# draft4_4lyr.net
KiCad netlist of a schematic drawn in EAGLE
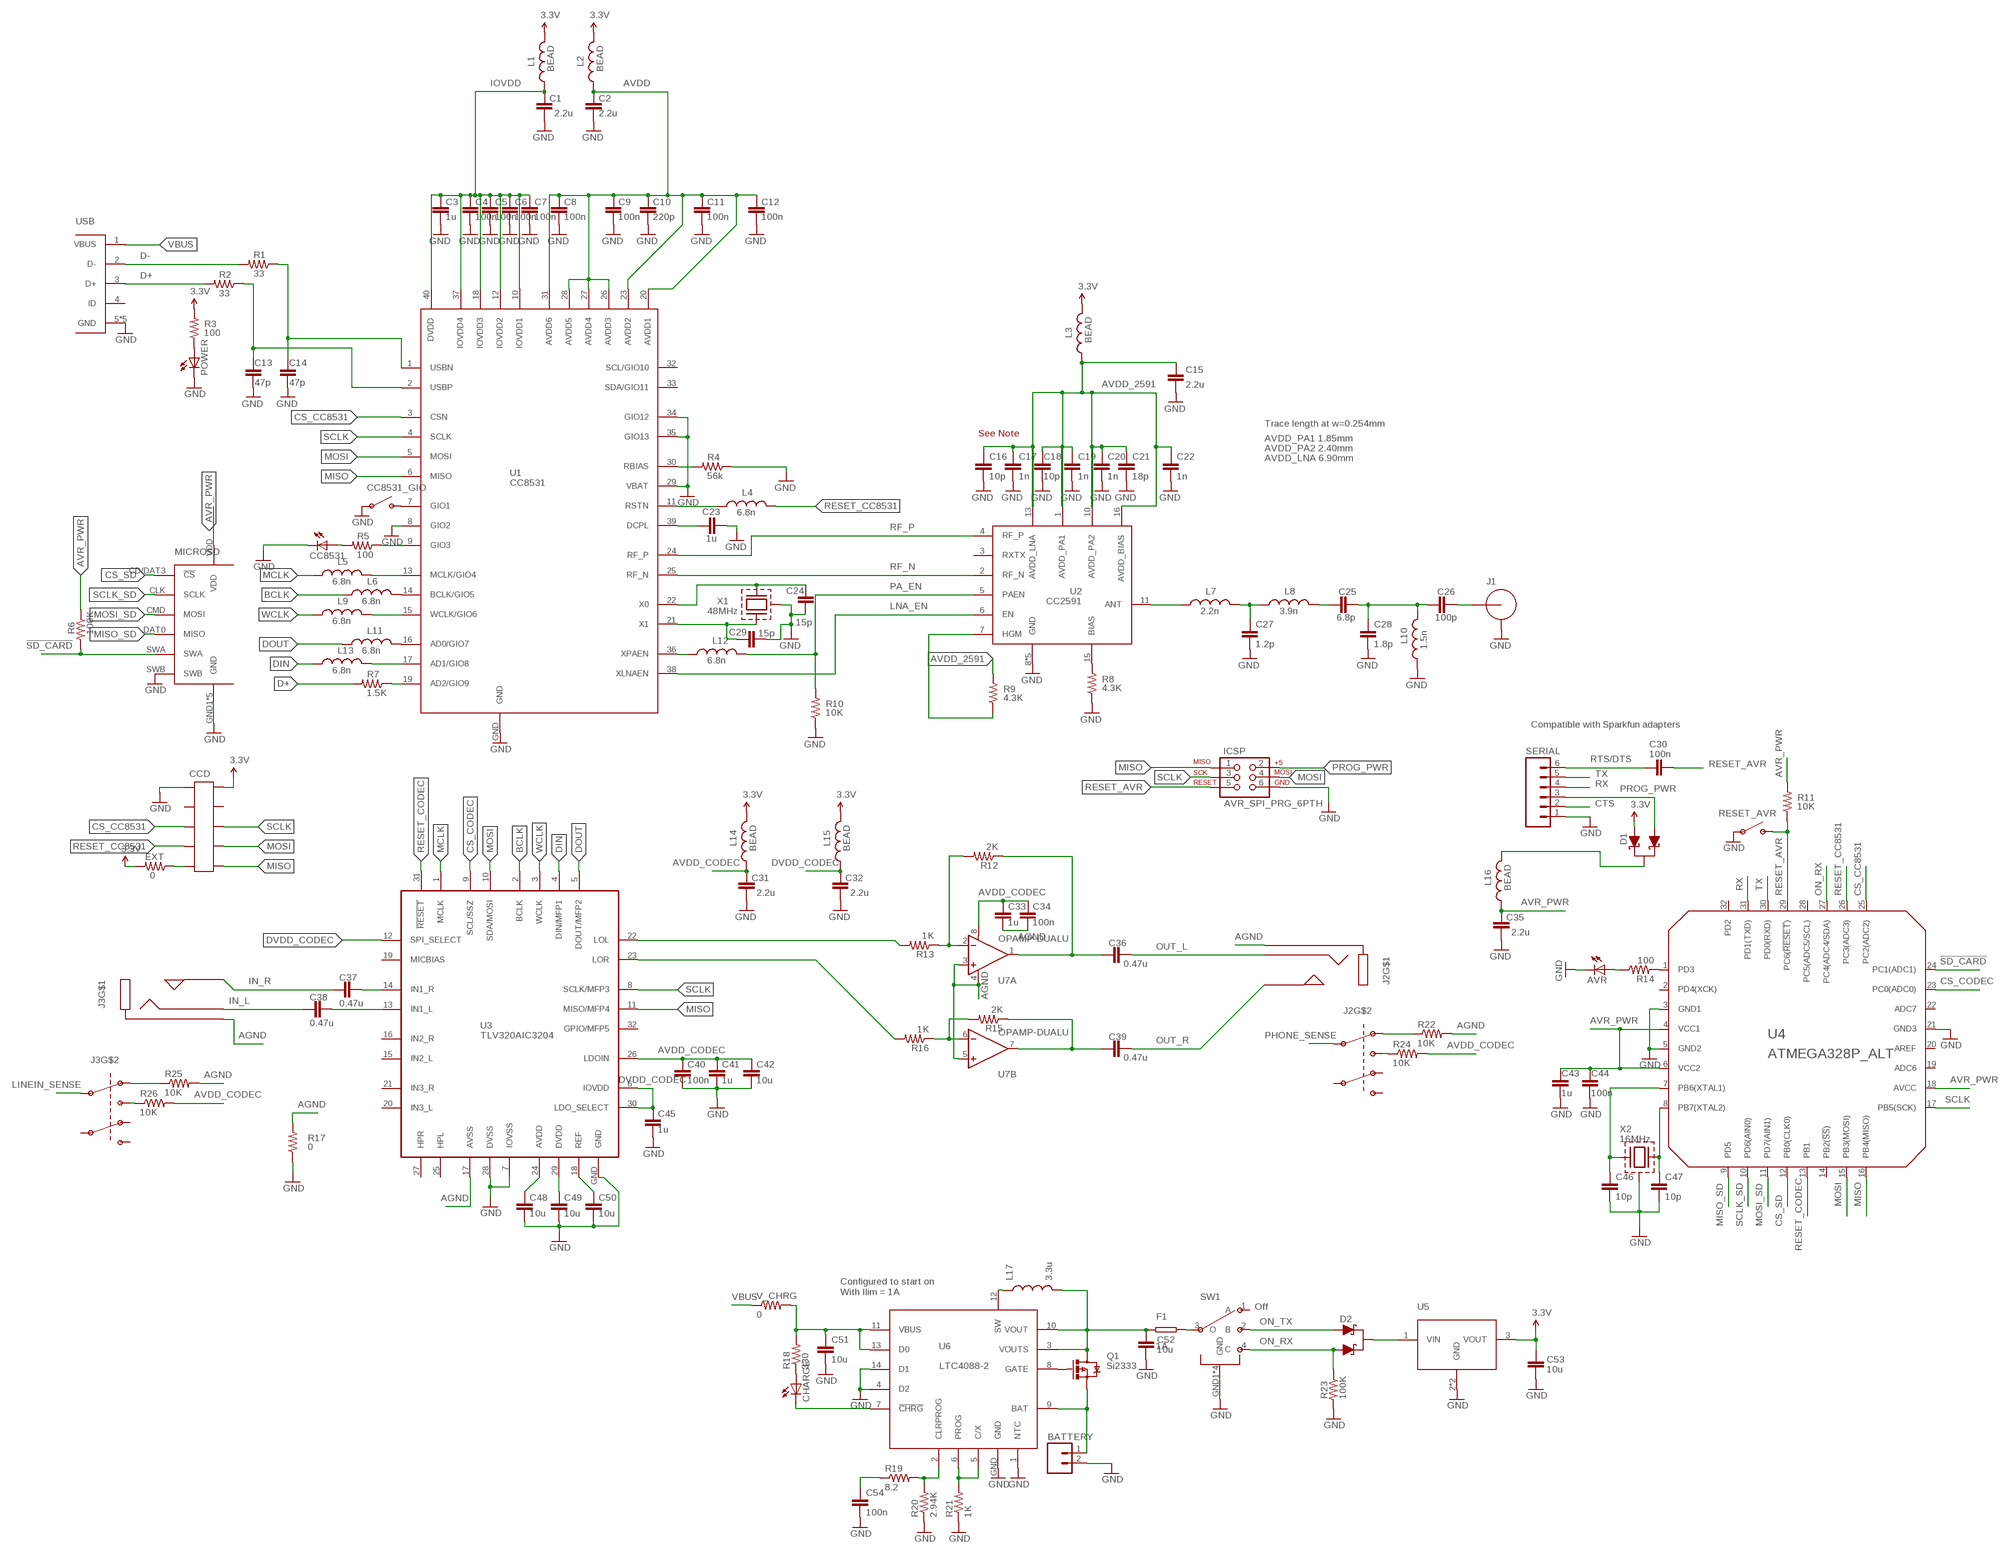
[diagram p0: schematic, sheet 1]

(export (version "E")
  (design (tool "Eeschema 10.0.6"))
  (components
    (comp (ref "AVR")
      (value "LED1206")
      (footprint "eagle-import:LED-1206")
      (libsource (lib "eagle-import") (part "LED1206"))
    )
    (comp (ref "BATTERY")
      (value "M02-JST-2MM-SMT")
      (footprint "eagle-import:JST-2-SMD")
      (libsource (lib "eagle-import") (part "M02-JST-2MM-SMT"))
    )
    (comp (ref "C1")
      (value "2.2u")
      (footprint "eagle-import:C0603")
      (libsource (lib "eagle-import") (part "rcl_C-EUC0603"))
    )
    (comp (ref "C2")
      (value "2.2u")
      (footprint "eagle-import:C0603")
      (libsource (lib "eagle-import") (part "rcl_C-EUC0603"))
    )
    (comp (ref "C3")
      (value "1u")
      (footprint "eagle-import:C0603")
      (libsource (lib "eagle-import") (part "rcl_C-EUC0603"))
    )
    (comp (ref "C4")
      (value "100n")
      (footprint "eagle-import:C0603")
      (libsource (lib "eagle-import") (part "rcl_C-EUC0603"))
    )
    (comp (ref "C5")
      (value "100n")
      (footprint "eagle-import:C0603")
      (libsource (lib "eagle-import") (part "rcl_C-EUC0603"))
    )
    (comp (ref "C6")
      (value "100n")
      (footprint "eagle-import:C0603")
      (libsource (lib "eagle-import") (part "rcl_C-EUC0603"))
    )
    (comp (ref "C7")
      (value "100n")
      (footprint "eagle-import:C0603")
      (libsource (lib "eagle-import") (part "rcl_C-EUC0603"))
    )
    (comp (ref "C8")
      (value "100n")
      (footprint "eagle-import:C0603")
      (libsource (lib "eagle-import") (part "rcl_C-EUC0603"))
    )
    (comp (ref "C9")
      (value "100n")
      (footprint "eagle-import:C0603")
      (libsource (lib "eagle-import") (part "rcl_C-EUC0603"))
    )
    (comp (ref "C10")
      (value "220p")
      (footprint "eagle-import:C0603")
      (libsource (lib "eagle-import") (part "rcl_C-EUC0603"))
    )
    (comp (ref "C11")
      (value "100n")
      (footprint "eagle-import:C0603")
      (libsource (lib "eagle-import") (part "rcl_C-EUC0603"))
    )
    (comp (ref "C12")
      (value "100n")
      (footprint "eagle-import:C0603")
      (libsource (lib "eagle-import") (part "rcl_C-EUC0603"))
    )
    (comp (ref "C13")
      (value "47p")
      (footprint "eagle-import:C0603")
      (libsource (lib "eagle-import") (part "rcl_C-EUC0603"))
    )
    (comp (ref "C14")
      (value "47p")
      (footprint "eagle-import:C0603")
      (libsource (lib "eagle-import") (part "rcl_C-EUC0603"))
    )
    (comp (ref "C15")
      (value "2.2u")
      (footprint "eagle-import:C0603")
      (libsource (lib "eagle-import") (part "rcl_C-EUC0603"))
    )
    (comp (ref "C16")
      (value "10p")
      (footprint "eagle-import:C0603")
      (libsource (lib "eagle-import") (part "rcl_C-EUC0603"))
    )
    (comp (ref "C17")
      (value "1n")
      (footprint "eagle-import:C0603")
      (libsource (lib "eagle-import") (part "rcl_C-EUC0603"))
    )
    (comp (ref "C18")
      (value "10p")
      (footprint "eagle-import:C0603")
      (libsource (lib "eagle-import") (part "rcl_C-EUC0603"))
    )
    (comp (ref "C19")
      (value "1n")
      (footprint "eagle-import:C0603")
      (libsource (lib "eagle-import") (part "rcl_C-EUC0603"))
    )
    (comp (ref "C20")
      (value "1n")
      (footprint "eagle-import:C0603")
      (libsource (lib "eagle-import") (part "rcl_C-EUC0603"))
    )
    (comp (ref "C21")
      (value "18p")
      (footprint "eagle-import:C0603")
      (libsource (lib "eagle-import") (part "rcl_C-EUC0603"))
    )
    (comp (ref "C22")
      (value "1n")
      (footprint "eagle-import:C0603")
      (libsource (lib "eagle-import") (part "rcl_C-EUC0603"))
    )
    (comp (ref "C23")
      (value "1u")
      (footprint "eagle-import:C0603")
      (libsource (lib "eagle-import") (part "rcl_C-EUC0603"))
    )
    (comp (ref "C24")
      (value "15p")
      (footprint "eagle-import:C0603")
      (libsource (lib "eagle-import") (part "rcl_C-EUC0603"))
    )
    (comp (ref "C25")
      (value "6.8p")
      (footprint "eagle-import:C0603")
      (libsource (lib "eagle-import") (part "rcl_C-EUC0603"))
    )
    (comp (ref "C26")
      (value "100p")
      (footprint "eagle-import:C0603")
      (libsource (lib "eagle-import") (part "rcl_C-EUC0603"))
    )
    (comp (ref "C27")
      (value "1.2p")
      (footprint "eagle-import:C0603")
      (libsource (lib "eagle-import") (part "rcl_C-EUC0603"))
    )
    (comp (ref "C28")
      (value "1.8p")
      (footprint "eagle-import:C0603")
      (libsource (lib "eagle-import") (part "rcl_C-EUC0603"))
    )
    (comp (ref "C29")
      (value "15p")
      (footprint "eagle-import:C0603")
      (libsource (lib "eagle-import") (part "rcl_C-EUC0603"))
    )
    (comp (ref "C30")
      (value "100n")
      (footprint "eagle-import:C0603")
      (libsource (lib "eagle-import") (part "rcl_C-EUC0603"))
    )
    (comp (ref "C31")
      (value "2.2u")
      (footprint "eagle-import:C0603")
      (libsource (lib "eagle-import") (part "rcl_C-EUC0603"))
    )
    (comp (ref "C32")
      (value "2.2u")
      (footprint "eagle-import:C0603")
      (libsource (lib "eagle-import") (part "rcl_C-EUC0603"))
    )
    (comp (ref "C33")
      (value "1u")
      (footprint "eagle-import:C0603")
      (libsource (lib "eagle-import") (part "rcl_C-EUC0603"))
    )
    (comp (ref "C34")
      (value "100n")
      (footprint "eagle-import:C0603")
      (libsource (lib "eagle-import") (part "rcl_C-EUC0603"))
    )
    (comp (ref "C35")
      (value "2.2u")
      (footprint "eagle-import:C0603")
      (libsource (lib "eagle-import") (part "rcl_C-EUC0603"))
    )
    (comp (ref "C36")
      (value "0.47u")
      (footprint "eagle-import:C0603")
      (libsource (lib "eagle-import") (part "rcl_C-EUC0603"))
    )
    (comp (ref "C37")
      (value "0.47u")
      (footprint "eagle-import:C0603")
      (libsource (lib "eagle-import") (part "rcl_C-EUC0603"))
    )
    (comp (ref "C38")
      (value "0.47u")
      (footprint "eagle-import:C0603")
      (libsource (lib "eagle-import") (part "rcl_C-EUC0603"))
    )
    (comp (ref "C39")
      (value "0.47u")
      (footprint "eagle-import:C0603")
      (libsource (lib "eagle-import") (part "rcl_C-EUC0603"))
    )
    (comp (ref "C40")
      (value "100n")
      (footprint "eagle-import:C0603")
      (libsource (lib "eagle-import") (part "rcl_C-EUC0603"))
    )
    (comp (ref "C41")
      (value "1u")
      (footprint "eagle-import:C0603")
      (libsource (lib "eagle-import") (part "rcl_C-EUC0603"))
    )
    (comp (ref "C42")
      (value "10u")
      (footprint "eagle-import:C0603")
      (libsource (lib "eagle-import") (part "rcl_C-EUC0603"))
    )
    (comp (ref "C43")
      (value "1u")
      (footprint "eagle-import:C0603")
      (libsource (lib "eagle-import") (part "rcl_C-EUC0603"))
    )
    (comp (ref "C44")
      (value "100n")
      (footprint "eagle-import:C0603")
      (libsource (lib "eagle-import") (part "rcl_C-EUC0603"))
    )
    (comp (ref "C45")
      (value "1u")
      (footprint "eagle-import:C0603")
      (libsource (lib "eagle-import") (part "rcl_C-EUC0603"))
    )
    (comp (ref "C46")
      (value "10p")
      (footprint "eagle-import:C0603")
      (libsource (lib "eagle-import") (part "C-EUC0603"))
    )
    (comp (ref "C47")
      (value "10p")
      (footprint "eagle-import:C0603")
      (libsource (lib "eagle-import") (part "C-EUC0603"))
    )
    (comp (ref "C48")
      (value "10u")
      (footprint "eagle-import:C0603")
      (libsource (lib "eagle-import") (part "rcl_C-EUC0603"))
    )
    (comp (ref "C49")
      (value "10u")
      (footprint "eagle-import:C0603")
      (libsource (lib "eagle-import") (part "rcl_C-EUC0603"))
    )
    (comp (ref "C50")
      (value "10u")
      (footprint "eagle-import:C0603")
      (libsource (lib "eagle-import") (part "rcl_C-EUC0603"))
    )
    (comp (ref "C51")
      (value "10u")
      (footprint "eagle-import:C0603")
      (libsource (lib "eagle-import") (part "C-EUC0603"))
    )
    (comp (ref "C52")
      (value "10u")
      (footprint "eagle-import:C0603")
      (libsource (lib "eagle-import") (part "rcl_C-EUC0603"))
    )
    (comp (ref "C53")
      (value "10u")
      (footprint "eagle-import:C0603")
      (libsource (lib "eagle-import") (part "rcl_C-EUC0603"))
    )
    (comp (ref "C54")
      (value "100n")
      (footprint "eagle-import:C0603")
      (libsource (lib "eagle-import") (part "C-EUC0603"))
    )
    (comp (ref "CC8531")
      (value "LED1206")
      (footprint "eagle-import:LED-1206")
      (libsource (lib "eagle-import") (part "LED1206"))
    )
    (comp (ref "CC8531_GIO")
      (value "SPST-SMD")
      (footprint "eagle-import:TACT_SW")
      (libsource (lib "eagle-import") (part "SPST-SMD"))
    )
    (comp (ref "CCD")
      (value "HEADER-10P-PTH-MALE")
      (footprint "eagle-import:2X5")
      (libsource (lib "eagle-import") (part "HEADER-10P-PTH-MALE"))
    )
    (comp (ref "CHARGE")
      (value "LED1206")
      (footprint "eagle-import:LED-1206")
      (libsource (lib "eagle-import") (part "LED1206"))
    )
    (comp (ref "D1")
      (value "DUAL_SCHOTTKY")
      (footprint "eagle-import:SOT-23")
      (libsource (lib "eagle-import") (part "DUAL_SCHOTTKY"))
    )
    (comp (ref "D2")
      (value "DUAL_SCHOTTKY")
      (footprint "eagle-import:SOT-23")
      (libsource (lib "eagle-import") (part "DUAL_SCHOTTKY"))
    )
    (comp (ref "EXT")
      (value "0")
      (footprint "eagle-import:R0603")
      (libsource (lib "eagle-import") (part "rcl_R-US_R0603"))
    )
    (comp (ref "F1")
      (value "1A")
      (footprint "eagle-import:1210")
      (libsource (lib "eagle-import") (part "PTC_FUSE"))
    )
    (comp (ref "ICSP")
      (value "AVR_SPI_PRG_6PTH")
      (footprint "eagle-import:2X3")
      (libsource (lib "eagle-import") (part "AVR_SPI_PRG_6PTH"))
    )
    (comp (ref "J1")
      (value "SMA")
      (footprint "eagle-import:CONSMA003.031")
      (libsource (lib "eagle-import") (part "SMA"))
    )
    (comp (ref "J2")
      (value "PHONE_DPDT")
      (footprint "eagle-import:STX-3100-9N")
      (libsource (lib "eagle-import") (part "PHONE_DPDT"))
    )
    (comp (ref "J3")
      (value "PHONE_DPDT")
      (footprint "eagle-import:STX-3100-9N")
      (libsource (lib "eagle-import") (part "PHONE_DPDT"))
    )
    (comp (ref "L1")
      (value "BEAD")
      (footprint "eagle-import:0603")
      (libsource (lib "eagle-import") (part "INDUCTOR0603"))
    )
    (comp (ref "L2")
      (value "BEAD")
      (footprint "eagle-import:0603")
      (libsource (lib "eagle-import") (part "INDUCTOR0603"))
    )
    (comp (ref "L3")
      (value "BEAD")
      (footprint "eagle-import:0603")
      (libsource (lib "eagle-import") (part "INDUCTOR0603"))
    )
    (comp (ref "L4")
      (value "6.8n")
      (footprint "eagle-import:0603")
      (libsource (lib "eagle-import") (part "INDUCTOR0603"))
    )
    (comp (ref "L5")
      (value "6.8n")
      (footprint "eagle-import:0603")
      (libsource (lib "eagle-import") (part "INDUCTOR0603"))
    )
    (comp (ref "L6")
      (value "6.8n")
      (footprint "eagle-import:0603")
      (libsource (lib "eagle-import") (part "INDUCTOR0603"))
    )
    (comp (ref "L7")
      (value "2.2n")
      (footprint "eagle-import:0603")
      (libsource (lib "eagle-import") (part "INDUCTOR0603"))
    )
    (comp (ref "L8")
      (value "3.9n")
      (footprint "eagle-import:0603")
      (libsource (lib "eagle-import") (part "INDUCTOR0603"))
    )
    (comp (ref "L9")
      (value "6.8n")
      (footprint "eagle-import:0603")
      (libsource (lib "eagle-import") (part "INDUCTOR0603"))
    )
    (comp (ref "L10")
      (value "1.5n")
      (footprint "eagle-import:0603")
      (libsource (lib "eagle-import") (part "INDUCTOR0603"))
    )
    (comp (ref "L11")
      (value "6.8n")
      (footprint "eagle-import:0603")
      (libsource (lib "eagle-import") (part "INDUCTOR0603"))
    )
    (comp (ref "L12")
      (value "6.8n")
      (footprint "eagle-import:0603")
      (libsource (lib "eagle-import") (part "INDUCTOR0603"))
    )
    (comp (ref "L13")
      (value "6.8n")
      (footprint "eagle-import:0603")
      (libsource (lib "eagle-import") (part "INDUCTOR0603"))
    )
    (comp (ref "L14")
      (value "BEAD")
      (footprint "eagle-import:0603")
      (libsource (lib "eagle-import") (part "INDUCTOR0603"))
    )
    (comp (ref "L15")
      (value "BEAD")
      (footprint "eagle-import:0603")
      (libsource (lib "eagle-import") (part "INDUCTOR0603"))
    )
    (comp (ref "L16")
      (value "BEAD")
      (footprint "eagle-import:0603")
      (libsource (lib "eagle-import") (part "INDUCTOR0603"))
    )
    (comp (ref "L17")
      (value "3.3u")
      (footprint "eagle-import:IFSC-1111AB-01")
      (libsource (lib "eagle-import") (part "IFSC-1111AB-01"))
    )
    (comp (ref "MICROSD")
      (value "MICROSD104031-0811")
      (footprint "eagle-import:MOLEX_104031-0811")
      (libsource (lib "eagle-import") (part "MICROSD104031-0811"))
    )
    (comp (ref "POWER")
      (value "LED1206")
      (footprint "eagle-import:LED-1206")
      (libsource (lib "eagle-import") (part "LED1206"))
    )
    (comp (ref "Q1")
      (value "Si2333")
      (footprint "eagle-import:SOT23-3")
      (libsource (lib "eagle-import") (part "MOSFET-PCHANNELSMD"))
    )
    (comp (ref "R1")
      (value "33")
      (footprint "eagle-import:R0603")
      (libsource (lib "eagle-import") (part "rcl_R-US_R0603"))
    )
    (comp (ref "R2")
      (value "33")
      (footprint "eagle-import:R0603")
      (libsource (lib "eagle-import") (part "rcl_R-US_R0603"))
    )
    (comp (ref "R3")
      (value "100")
      (footprint "eagle-import:R0603")
      (libsource (lib "eagle-import") (part "rcl_R-US_R0603"))
    )
    (comp (ref "R4")
      (value "56k")
      (footprint "eagle-import:R0603")
      (libsource (lib "eagle-import") (part "rcl_R-US_R0603"))
    )
    (comp (ref "R5")
      (value "100")
      (footprint "eagle-import:R0603")
      (libsource (lib "eagle-import") (part "rcl_R-US_R0603"))
    )
    (comp (ref "R6")
      (value "100K")
      (footprint "eagle-import:R0603")
      (libsource (lib "eagle-import") (part "rcl_R-US_R0603"))
    )
    (comp (ref "R7")
      (value "1.5K")
      (footprint "eagle-import:R0603")
      (libsource (lib "eagle-import") (part "rcl_R-US_R0603"))
    )
    (comp (ref "R8")
      (value "4.3K")
      (footprint "eagle-import:R0603")
      (libsource (lib "eagle-import") (part "rcl_R-US_R0603"))
    )
    (comp (ref "R9")
      (value "4.3K")
      (footprint "eagle-import:R0603")
      (libsource (lib "eagle-import") (part "rcl_R-US_R0603"))
    )
    (comp (ref "R10")
      (value "10K")
      (footprint "eagle-import:R0603")
      (libsource (lib "eagle-import") (part "rcl_R-US_R0603"))
    )
    (comp (ref "R11")
      (value "10K")
      (footprint "eagle-import:R0603")
      (libsource (lib "eagle-import") (part "rcl_R-US_R0603"))
    )
    (comp (ref "R12")
      (value "2K")
      (footprint "eagle-import:R0603")
      (libsource (lib "eagle-import") (part "R-US_R0603"))
    )
    (comp (ref "R13")
      (value "1K")
      (footprint "eagle-import:R0603")
      (libsource (lib "eagle-import") (part "R-US_R0603"))
    )
    (comp (ref "R14")
      (value "100")
      (footprint "eagle-import:R0603")
      (libsource (lib "eagle-import") (part "rcl_R-US_R0603"))
    )
    (comp (ref "R15")
      (value "2K")
      (footprint "eagle-import:R0603")
      (libsource (lib "eagle-import") (part "R-US_R0603"))
    )
    (comp (ref "R16")
      (value "1K")
      (footprint "eagle-import:R0603")
      (libsource (lib "eagle-import") (part "R-US_R0603"))
    )
    (comp (ref "R17")
      (value "0")
      (footprint "eagle-import:R0603")
      (libsource (lib "eagle-import") (part "rcl_R-US_R0603"))
    )
    (comp (ref "R18")
      (value "330")
      (footprint "eagle-import:R0603")
      (libsource (lib "eagle-import") (part "R-US_R0603"))
    )
    (comp (ref "R19")
      (value "8.2")
      (footprint "eagle-import:R0603")
      (libsource (lib "eagle-import") (part "R-US_R0603"))
    )
    (comp (ref "R20")
      (value "2.94K")
      (footprint "eagle-import:R0603")
      (libsource (lib "eagle-import") (part "R-US_R0603"))
    )
    (comp (ref "R21")
      (value "1K")
      (footprint "eagle-import:R0603")
      (libsource (lib "eagle-import") (part "R-US_R0603"))
    )
    (comp (ref "R22")
      (value "10K")
      (footprint "eagle-import:R0603")
      (libsource (lib "eagle-import") (part "R-US_R0603"))
    )
    (comp (ref "R23")
      (value "100K")
      (footprint "eagle-import:R0603")
      (libsource (lib "eagle-import") (part "rcl_R-US_R0603"))
    )
    (comp (ref "R24")
      (value "10K")
      (footprint "eagle-import:R0603")
      (libsource (lib "eagle-import") (part "R-US_R0603"))
    )
    (comp (ref "R25")
      (value "10K")
      (footprint "eagle-import:R0603")
      (libsource (lib "eagle-import") (part "R-US_R0603"))
    )
    (comp (ref "R26")
      (value "10K")
      (footprint "eagle-import:R0603")
      (libsource (lib "eagle-import") (part "R-US_R0603"))
    )
    (comp (ref "RESET_AVR")
      (value "SPST-SMD")
      (footprint "eagle-import:TACT_SW")
      (libsource (lib "eagle-import") (part "SPST-SMD"))
    )
    (comp (ref "SERIAL")
      (value "M06SIP")
      (footprint "eagle-import:1X06")
      (libsource (lib "eagle-import") (part "M06SIP"))
    )
    (comp (ref "SW1")
      (value "SP3T-SSSS812201")
      (footprint "eagle-import:SSSS812201")
      (libsource (lib "eagle-import") (part "SP3T-SSSS812201"))
    )
    (comp (ref "U1")
      (value "CC8531")
      (footprint "eagle-import:S-PVQFN-N40")
      (libsource (lib "eagle-import") (part "CC8531"))
    )
    (comp (ref "U2")
      (value "CC2591")
      (footprint "eagle-import:S-PVQFN-N16")
      (libsource (lib "eagle-import") (part "CC2591"))
    )
    (comp (ref "U3")
      (value "TLV320AIC3204")
      (footprint "eagle-import:S-PVQFN-N32")
      (libsource (lib "eagle-import") (part "TLV320AIC3204"))
    )
    (comp (ref "U4")
      (value "ATMEGA328P_ALT")
      (footprint "eagle-import:S-PQFP-N32")
      (libsource (lib "eagle-import") (part "ATMEGA328P_ALT"))
    )
    (comp (ref "U5")
      (value "MCP1826-SOT223")
      (footprint "eagle-import:SOT-223")
      (libsource (lib "eagle-import") (part "MCP1826-SOT223"))
    )
    (comp (ref "U6")
      (value "LTC4088-2")
      (footprint "eagle-import:DFN-14")
      (libsource (lib "eagle-import") (part "LTC4088-1/2"))
    )
    (comp (ref "U7")
      (value "OPAMP-DUALU")
      (footprint "eagle-import:SO08")
      (libsource (lib "eagle-import") (part "OPAMP-DUALU"))
    )
    (comp (ref "USB")
      (value "USB_MICRO_AB")
      (footprint "eagle-import:USB_MICRO_AB")
      (libsource (lib "eagle-import") (part "USB_MICRO_AB"))
    )
    (comp (ref "V_CHRG")
      (value "0")
      (footprint "eagle-import:R0603")
      (libsource (lib "eagle-import") (part "R-US_R0603"))
    )
    (comp (ref "X1")
      (value "48MHz")
      (footprint "eagle-import:ABM3C")
      (libsource (lib "eagle-import") (part "XTAL-ABRACONABM3C"))
    )
    (comp (ref "X2")
      (value "16MHz")
      (footprint "eagle-import:ABM8G")
      (libsource (lib "eagle-import") (part "XTAL-ABRACONABM8G"))
    )
  )
  (nets
    (net (code "1") (name "/AGND") (class "Default")
      (node (ref "C33") (pin "2") (pinfunction "2_2") (pintype "passive"))
      (node (ref "C34") (pin "2") (pinfunction "2_2") (pintype "passive"))
      (node (ref "J2") (pin "1") (pinfunction "GND_1") (pintype "bidirectional"))
      (node (ref "J3") (pin "1") (pinfunction "GND_1") (pintype "bidirectional"))
      (node (ref "R17") (pin "2") (pinfunction "2_2") (pintype "passive"))
      (node (ref "R22") (pin "2") (pinfunction "2_2") (pintype "passive"))
      (node (ref "R25") (pin "2") (pinfunction "2_2") (pintype "passive"))
      (node (ref "U3") (pin "17") (pinfunction "AVSS_17") (pintype "bidirectional"))
      (node (ref "U7") (pin "3") (pinfunction "+IN_3") (pintype "input"))
      (node (ref "U7") (pin "4") (pinfunction "V-_4") (pintype "power_in"))
      (node (ref "U7") (pin "5") (pinfunction "+IN_5") (pintype "input"))
    )
    (net (code "2") (name "/AVDD") (class "Default")
      (node (ref "C10") (pin "1") (pinfunction "1_1") (pintype "passive"))
      (node (ref "C11") (pin "1") (pinfunction "1_1") (pintype "passive"))
      (node (ref "C12") (pin "1") (pinfunction "1_1") (pintype "passive"))
      (node (ref "C2") (pin "1") (pinfunction "1_1") (pintype "passive"))
      (node (ref "C8") (pin "1") (pinfunction "1_1") (pintype "passive"))
      (node (ref "C9") (pin "1") (pinfunction "1_1") (pintype "passive"))
      (node (ref "L2") (pin "1") (pinfunction "1_1") (pintype "passive"))
      (node (ref "U1") (pin "20") (pinfunction "AVDD1_20") (pintype "bidirectional"))
      (node (ref "U1") (pin "23") (pinfunction "AVDD2_23") (pintype "bidirectional"))
      (node (ref "U1") (pin "26") (pinfunction "AVDD3_26") (pintype "bidirectional"))
      (node (ref "U1") (pin "27") (pinfunction "AVDD4_27") (pintype "bidirectional"))
      (node (ref "U1") (pin "28") (pinfunction "AVDD5_28") (pintype "bidirectional"))
      (node (ref "U1") (pin "31") (pinfunction "AVDD6_31") (pintype "bidirectional"))
    )
    (net (code "3") (name "/AVDD_CODEC") (class "Default")
      (node (ref "C31") (pin "1") (pinfunction "1_1") (pintype "passive"))
      (node (ref "C33") (pin "1") (pinfunction "1_1") (pintype "passive"))
      (node (ref "C34") (pin "1") (pinfunction "1_1") (pintype "passive"))
      (node (ref "C40") (pin "1") (pinfunction "1_1") (pintype "passive"))
      (node (ref "C41") (pin "1") (pinfunction "1_1") (pintype "passive"))
      (node (ref "C42") (pin "1") (pinfunction "1_1") (pintype "passive"))
      (node (ref "L14") (pin "1") (pinfunction "1_1") (pintype "passive"))
      (node (ref "R24") (pin "2") (pinfunction "2_2") (pintype "passive"))
      (node (ref "R26") (pin "2") (pinfunction "2_2") (pintype "passive"))
      (node (ref "U3") (pin "26") (pinfunction "LDOIN_26") (pintype "bidirectional"))
      (node (ref "U7") (pin "8") (pinfunction "V+_8") (pintype "power_in"))
    )
    (net (code "4") (name "/CTS") (class "Default")
      (node (ref "SERIAL") (pin "2") (pinfunction "2_2") (pintype "passive"))
    )
    (net (code "5") (name "/D-") (class "Default")
      (node (ref "R1") (pin "2") (pinfunction "2_2") (pintype "passive"))
      (node (ref "USB") (pin "2") (pinfunction "D-_2") (pintype "bidirectional"))
    )
    (net (code "6") (name "/IN_L") (class "Default")
      (node (ref "C38") (pin "1") (pinfunction "1_1") (pintype "passive"))
      (node (ref "J3") (pin "3") (pinfunction "R_3") (pintype "bidirectional"))
    )
    (net (code "7") (name "/IN_R") (class "Default")
      (node (ref "C37") (pin "1") (pinfunction "1_1") (pintype "passive"))
      (node (ref "J3") (pin "2") (pinfunction "L_2") (pintype "bidirectional"))
    )
    (net (code "8") (name "/IOVDD") (class "Default")
      (node (ref "C1") (pin "1") (pinfunction "1_1") (pintype "passive"))
      (node (ref "C3") (pin "1") (pinfunction "1_1") (pintype "passive"))
      (node (ref "C4") (pin "1") (pinfunction "1_1") (pintype "passive"))
      (node (ref "C5") (pin "1") (pinfunction "1_1") (pintype "passive"))
      (node (ref "C6") (pin "1") (pinfunction "1_1") (pintype "passive"))
      (node (ref "C7") (pin "1") (pinfunction "1_1") (pintype "passive"))
      (node (ref "L1") (pin "1") (pinfunction "1_1") (pintype "passive"))
      (node (ref "U1") (pin "10") (pinfunction "IOVDD1_10") (pintype "bidirectional"))
      (node (ref "U1") (pin "12") (pinfunction "IOVDD2_12") (pintype "bidirectional"))
      (node (ref "U1") (pin "18") (pinfunction "IOVDD3_18") (pintype "bidirectional"))
      (node (ref "U1") (pin "37") (pinfunction "IOVDD4_37") (pintype "bidirectional"))
      (node (ref "U1") (pin "40") (pinfunction "DVDD_40") (pintype "bidirectional"))
    )
    (net (code "9") (name "/LINEIN_SENSE") (class "Default")
      (node (ref "J3") (pin "7") (pinfunction "S1_7") (pintype "bidirectional"))
    )
    (net (code "10") (name "/LNA_EN") (class "Default")
      (node (ref "U1") (pin "38") (pinfunction "XLNAEN_38") (pintype "bidirectional"))
      (node (ref "U2") (pin "6") (pinfunction "EN_6") (pintype "bidirectional"))
    )
    (net (code "11") (name "/ON_RX") (class "Default")
      (node (ref "D2") (pin "2") (pinfunction "A_2") (pintype "passive"))
      (node (ref "R23") (pin "1") (pinfunction "1_1") (pintype "passive"))
      (node (ref "SW1") (pin "4") (pinfunction "C_4") (pintype "bidirectional"))
      (node (ref "U4") (pin "27") (pinfunction "PC4(ADC4/SDA)_27") (pintype "bidirectional"))
    )
    (net (code "12") (name "/ON_TX") (class "Default")
      (node (ref "D2") (pin "1") (pinfunction "A1_1") (pintype "passive"))
      (node (ref "SW1") (pin "2") (pinfunction "B_2") (pintype "bidirectional"))
    )
    (net (code "13") (name "/OUT_L") (class "Default")
      (node (ref "C36") (pin "2") (pinfunction "2_2") (pintype "passive"))
      (node (ref "J2") (pin "3") (pinfunction "R_3") (pintype "bidirectional"))
    )
    (net (code "14") (name "/OUT_R") (class "Default")
      (node (ref "C39") (pin "2") (pinfunction "2_2") (pintype "passive"))
      (node (ref "J2") (pin "2") (pinfunction "L_2") (pintype "bidirectional"))
    )
    (net (code "15") (name "/PA_EN") (class "Default")
      (node (ref "L12") (pin "2") (pinfunction "2_2") (pintype "passive"))
      (node (ref "R10") (pin "2") (pinfunction "2_2") (pintype "passive"))
      (node (ref "U2") (pin "5") (pinfunction "PAEN_5") (pintype "bidirectional"))
    )
    (net (code "16") (name "/PHONE_SENSE") (class "Default")
      (node (ref "J2") (pin "7") (pinfunction "S1_7") (pintype "bidirectional"))
    )
    (net (code "17") (name "/RF_N") (class "Default")
      (node (ref "U1") (pin "25") (pinfunction "RF_N_25") (pintype "bidirectional"))
      (node (ref "U2") (pin "2") (pinfunction "RF_N_2") (pintype "bidirectional"))
    )
    (net (code "18") (name "/RF_P") (class "Default")
      (node (ref "U1") (pin "24") (pinfunction "RF_P_24") (pintype "bidirectional"))
      (node (ref "U2") (pin "4") (pinfunction "RF_P_4") (pintype "bidirectional"))
    )
    (net (code "19") (name "/RTS{slash}DTS") (class "Default")
      (node (ref "C30") (pin "1") (pinfunction "1_1") (pintype "passive"))
      (node (ref "SERIAL") (pin "6") (pinfunction "6_6") (pintype "passive"))
    )
    (net (code "20") (name "/RX") (class "Default")
      (node (ref "SERIAL") (pin "4") (pinfunction "4_4") (pintype "passive"))
      (node (ref "U4") (pin "31") (pinfunction "PD1(TXD)_31") (pintype "bidirectional"))
    )
    (net (code "21") (name "/TX") (class "Default")
      (node (ref "SERIAL") (pin "5") (pinfunction "5_5") (pintype "passive"))
      (node (ref "U4") (pin "30") (pinfunction "PD0(RXD)_30") (pintype "bidirectional"))
    )
    (net (code "22") (name "/~{SD_CARD}") (class "Default")
      (node (ref "MICROSD") (pin "SWA") (pinfunction "SWA_SWA") (pintype "bidirectional"))
      (node (ref "R6") (pin "2") (pinfunction "2_2") (pintype "passive"))
      (node (ref "U4") (pin "24") (pinfunction "PC1(ADC1)_24") (pintype "bidirectional"))
    )
    (net (code "23") (name "3.3V") (class "Default")
      (node (ref "C53") (pin "1") (pinfunction "1_1") (pintype "passive"))
      (node (ref "CCD") (pin "2") (pinfunction "2_2") (pintype "bidirectional"))
      (node (ref "D1") (pin "1") (pinfunction "A1_1") (pintype "passive"))
      (node (ref "EXT") (pin "2") (pinfunction "2_2") (pintype "passive"))
      (node (ref "L1") (pin "2") (pinfunction "2_2") (pintype "passive"))
      (node (ref "L14") (pin "2") (pinfunction "2_2") (pintype "passive"))
      (node (ref "L15") (pin "2") (pinfunction "2_2") (pintype "passive"))
      (node (ref "L2") (pin "2") (pinfunction "2_2") (pintype "passive"))
      (node (ref "L3") (pin "2") (pinfunction "2_2") (pintype "passive"))
      (node (ref "R3") (pin "2") (pinfunction "2_2") (pintype "passive"))
      (node (ref "U5") (pin "3") (pinfunction "VOUT_3") (pintype "bidirectional"))
    )
    (net (code "24") (name "AVDD_2591") (class "Default")
      (node (ref "C15") (pin "1") (pinfunction "1_1") (pintype "passive"))
      (node (ref "C16") (pin "1") (pinfunction "1_1") (pintype "passive"))
      (node (ref "C17") (pin "1") (pinfunction "1_1") (pintype "passive"))
      (node (ref "C18") (pin "1") (pinfunction "1_1") (pintype "passive"))
      (node (ref "C19") (pin "1") (pinfunction "1_1") (pintype "passive"))
      (node (ref "C20") (pin "1") (pinfunction "1_1") (pintype "passive"))
      (node (ref "C21") (pin "1") (pinfunction "1_1") (pintype "passive"))
      (node (ref "C22") (pin "1") (pinfunction "1_1") (pintype "passive"))
      (node (ref "L3") (pin "1") (pinfunction "1_1") (pintype "passive"))
      (node (ref "R9") (pin "2") (pinfunction "2_2") (pintype "passive"))
      (node (ref "U2") (pin "1") (pinfunction "AVDD_PA1_1") (pintype "bidirectional"))
      (node (ref "U2") (pin "10") (pinfunction "AVDD_PA2_10") (pintype "bidirectional"))
      (node (ref "U2") (pin "13") (pinfunction "AVDD_LNA_13") (pintype "bidirectional"))
      (node (ref "U2") (pin "16") (pinfunction "AVDD_BIAS_16") (pintype "bidirectional"))
    )
    (net (code "25") (name "AVR_PWR") (class "Default")
      (node (ref "C35") (pin "1") (pinfunction "1_1") (pintype "passive"))
      (node (ref "C43") (pin "1") (pinfunction "1_1") (pintype "passive"))
      (node (ref "C44") (pin "1") (pinfunction "1_1") (pintype "passive"))
      (node (ref "L16") (pin "1") (pinfunction "1_1") (pintype "passive"))
      (node (ref "MICROSD") (pin "VDD") (pinfunction "VDD_VDD") (pintype "bidirectional"))
      (node (ref "R11") (pin "2") (pinfunction "2_2") (pintype "passive"))
      (node (ref "R6") (pin "1") (pinfunction "1_1") (pintype "passive"))
      (node (ref "U4") (pin "18") (pinfunction "AVCC_18") (pintype "bidirectional"))
      (node (ref "U4") (pin "4") (pinfunction "VCC1_4") (pintype "bidirectional"))
      (node (ref "U4") (pin "6") (pinfunction "VCC2_6") (pintype "bidirectional"))
    )
    (net (code "26") (name "BCLK") (class "Default")
      (node (ref "L6") (pin "1") (pinfunction "1_1") (pintype "passive"))
      (node (ref "U3") (pin "2") (pinfunction "BCLK_2") (pintype "bidirectional"))
    )
    (net (code "27") (name "CS_CC8531") (class "Default")
      (node (ref "CCD") (pin "5") (pinfunction "5_5") (pintype "bidirectional"))
      (node (ref "U1") (pin "3") (pinfunction "CSN_3") (pintype "bidirectional"))
      (node (ref "U4") (pin "25") (pinfunction "PC2(ADC2)_25") (pintype "bidirectional"))
    )
    (net (code "28") (name "CS_CODEC") (class "Default")
      (node (ref "U3") (pin "9") (pinfunction "SCL/SSZ_9") (pintype "bidirectional"))
      (node (ref "U4") (pin "23") (pinfunction "PC0(ADC0)_23") (pintype "bidirectional"))
    )
    (net (code "29") (name "CS_SD") (class "Default")
      (node (ref "MICROSD") (pin "CD/DAT3") (pinfunction "~{CS}_CD/DAT3") (pintype "bidirectional"))
      (node (ref "U4") (pin "12") (pinfunction "PB0(CLK0)_12") (pintype "bidirectional"))
    )
    (net (code "30") (name "D+") (class "Default")
      (node (ref "R2") (pin "2") (pinfunction "2_2") (pintype "passive"))
      (node (ref "R7") (pin "2") (pinfunction "2_2") (pintype "passive"))
      (node (ref "USB") (pin "3") (pinfunction "D+_3") (pintype "bidirectional"))
    )
    (net (code "31") (name "DIN") (class "Default")
      (node (ref "L13") (pin "1") (pinfunction "1_1") (pintype "passive"))
      (node (ref "U3") (pin "4") (pinfunction "DIN/MFP1_4") (pintype "bidirectional"))
    )
    (net (code "32") (name "DOUT") (class "Default")
      (node (ref "L11") (pin "1") (pinfunction "1_1") (pintype "passive"))
      (node (ref "U3") (pin "5") (pinfunction "DOUT/MFP2_5") (pintype "bidirectional"))
    )
    (net (code "33") (name "DVDD_CODEC") (class "Default")
      (node (ref "C32") (pin "1") (pinfunction "1_1") (pintype "passive"))
      (node (ref "C45") (pin "1") (pinfunction "1_1") (pintype "passive"))
      (node (ref "L15") (pin "1") (pinfunction "1_1") (pintype "passive"))
      (node (ref "U3") (pin "12") (pinfunction "SPI_SELECT_12") (pintype "bidirectional"))
      (node (ref "U3") (pin "30") (pinfunction "LDO_SELECT_30") (pintype "bidirectional"))
      (node (ref "U3") (pin "6") (pinfunction "IOVDD_6") (pintype "bidirectional"))
    )
    (net (code "34") (name "GND") (class "Default")
      (node (ref "AVR") (pin "C") (pinfunction "C_C") (pintype "passive"))
      (node (ref "BATTERY") (pin "2") (pinfunction "1_2") (pintype "passive"))
      (node (ref "C1") (pin "2") (pinfunction "2_2") (pintype "passive"))
      (node (ref "C10") (pin "2") (pinfunction "2_2") (pintype "passive"))
      (node (ref "C11") (pin "2") (pinfunction "2_2") (pintype "passive"))
      (node (ref "C12") (pin "2") (pinfunction "2_2") (pintype "passive"))
      (node (ref "C13") (pin "2") (pinfunction "2_2") (pintype "passive"))
      (node (ref "C14") (pin "2") (pinfunction "2_2") (pintype "passive"))
      (node (ref "C15") (pin "2") (pinfunction "2_2") (pintype "passive"))
      (node (ref "C16") (pin "2") (pinfunction "2_2") (pintype "passive"))
      (node (ref "C17") (pin "2") (pinfunction "2_2") (pintype "passive"))
      (node (ref "C18") (pin "2") (pinfunction "2_2") (pintype "passive"))
      (node (ref "C19") (pin "2") (pinfunction "2_2") (pintype "passive"))
      (node (ref "C2") (pin "2") (pinfunction "2_2") (pintype "passive"))
      (node (ref "C20") (pin "2") (pinfunction "2_2") (pintype "passive"))
      (node (ref "C21") (pin "2") (pinfunction "2_2") (pintype "passive"))
      (node (ref "C22") (pin "2") (pinfunction "2_2") (pintype "passive"))
      (node (ref "C23") (pin "2") (pinfunction "2_2") (pintype "passive"))
      (node (ref "C24") (pin "2") (pinfunction "2_2") (pintype "passive"))
      (node (ref "C27") (pin "2") (pinfunction "2_2") (pintype "passive"))
      (node (ref "C28") (pin "2") (pinfunction "2_2") (pintype "passive"))
      (node (ref "C29") (pin "2") (pinfunction "2_2") (pintype "passive"))
      (node (ref "C3") (pin "2") (pinfunction "2_2") (pintype "passive"))
      (node (ref "C31") (pin "2") (pinfunction "2_2") (pintype "passive"))
      (node (ref "C32") (pin "2") (pinfunction "2_2") (pintype "passive"))
      (node (ref "C35") (pin "2") (pinfunction "2_2") (pintype "passive"))
      (node (ref "C4") (pin "2") (pinfunction "2_2") (pintype "passive"))
      (node (ref "C40") (pin "2") (pinfunction "2_2") (pintype "passive"))
      (node (ref "C41") (pin "2") (pinfunction "2_2") (pintype "passive"))
      (node (ref "C42") (pin "2") (pinfunction "2_2") (pintype "passive"))
      (node (ref "C43") (pin "2") (pinfunction "2_2") (pintype "passive"))
      (node (ref "C44") (pin "2") (pinfunction "2_2") (pintype "passive"))
      (node (ref "C45") (pin "2") (pinfunction "2_2") (pintype "passive"))
      (node (ref "C46") (pin "2") (pinfunction "2_2") (pintype "passive"))
      (node (ref "C47") (pin "2") (pinfunction "2_2") (pintype "passive"))
      (node (ref "C48") (pin "2") (pinfunction "2_2") (pintype "passive"))
      (node (ref "C49") (pin "2") (pinfunction "2_2") (pintype "passive"))
      (node (ref "C5") (pin "2") (pinfunction "2_2") (pintype "passive"))
      (node (ref "C50") (pin "2") (pinfunction "2_2") (pintype "passive"))
      (node (ref "C51") (pin "2") (pinfunction "2_2") (pintype "passive"))
      (node (ref "C52") (pin "2") (pinfunction "2_2") (pintype "passive"))
      (node (ref "C53") (pin "2") (pinfunction "2_2") (pintype "passive"))
      (node (ref "C54") (pin "2") (pinfunction "2_2") (pintype "passive"))
      (node (ref "C6") (pin "2") (pinfunction "2_2") (pintype "passive"))
      (node (ref "C7") (pin "2") (pinfunction "2_2") (pintype "passive"))
      (node (ref "C8") (pin "2") (pinfunction "2_2") (pintype "passive"))
      (node (ref "C9") (pin "2") (pinfunction "2_2") (pintype "passive"))
      (node (ref "CC8531") (pin "C") (pinfunction "C_C") (pintype "passive"))
      (node (ref "CC8531_GIO") (pin "1") (pinfunction "P$1_1") (pintype "bidirectional"))
      (node (ref "CC8531_GIO") (pin "2") (pinfunction "P$1_2") (pintype "bidirectional"))
      (node (ref "CCD") (pin "1") (pinfunction "1_1") (pintype "bidirectional"))
      (node (ref "ICSP") (pin "6") (pinfunction "6_6") (pintype "passive"))
      (node (ref "J1") (pin "GND1") (pinfunction "GND_GND1") (pintype "bidirectional"))
      (node (ref "J1") (pin "GND2") (pinfunction "GND_GND2") (pintype "bidirectional"))
      (node (ref "J1") (pin "GND3") (pinfunction "GND_GND3") (pintype "bidirectional"))
      (node (ref "J1") (pin "GND4") (pinfunction "GND_GND4") (pintype "bidirectional"))
      (node (ref "L10") (pin "1") (pinfunction "1_1") (pintype "passive"))
      (node (ref "MICROSD") (pin "GND1") (pinfunction "GND_GND1") (pintype "bidirectional"))
      (node (ref "MICROSD") (pin "GND2") (pinfunction "GND_GND2") (pintype "bidirectional"))
      (node (ref "MICROSD") (pin "GND3") (pinfunction "GND_GND3") (pintype "bidirectional"))
      (node (ref "MICROSD") (pin "GND4") (pinfunction "GND_GND4") (pintype "bidirectional"))
      (node (ref "MICROSD") (pin "SWB") (pinfunction "SWB_SWB") (pintype "bidirectional"))
      (node (ref "MICROSD") (pin "VSS") (pinfunction "GND_VSS") (pintype "bidirectional"))
      (node (ref "POWER") (pin "C") (pinfunction "C_C") (pintype "passive"))
      (node (ref "R10") (pin "1") (pinfunction "1_1") (pintype "passive"))
      (node (ref "R17") (pin "1") (pinfunction "1_1") (pintype "passive"))
      (node (ref "R20") (pin "1") (pinfunction "1_1") (pintype "passive"))
      (node (ref "R21") (pin "1") (pinfunction "1_1") (pintype "passive"))
      (node (ref "R23") (pin "2") (pinfunction "2_2") (pintype "passive"))
      (node (ref "R4") (pin "1") (pinfunction "1_1") (pintype "passive"))
      (node (ref "R8") (pin "1") (pinfunction "1_1") (pintype "passive"))
      (node (ref "RESET_AVR") (pin "1") (pinfunction "P$1_1") (pintype "bidirectional"))
      (node (ref "RESET_AVR") (pin "2") (pinfunction "P$1_2") (pintype "bidirectional"))
      (node (ref "SERIAL") (pin "1") (pinfunction "1_1") (pintype "passive"))
      (node (ref "SW1") (pin "GND1") (pinfunction "GND_GND1") (pintype "bidirectional"))
      (node (ref "SW1") (pin "GND2") (pinfunction "GND_GND2") (pintype "bidirectional"))
      (node (ref "SW1") (pin "GND3") (pinfunction "GND_GND3") (pintype "bidirectional"))
      (node (ref "SW1") (pin "GND4") (pinfunction "GND_GND4") (pintype "bidirectional"))
      (node (ref "U1") (pin "29") (pinfunction "VBAT_29") (pintype "bidirectional"))
      (node (ref "U1") (pin "34") (pinfunction "GIO12_34") (pintype "bidirectional"))
      (node (ref "U1") (pin "35") (pinfunction "GIO13_35") (pintype "bidirectional"))
      (node (ref "U1") (pin "8") (pinfunction "GIO2_8") (pintype "bidirectional"))
      (node (ref "U1") (pin "GND") (pinfunction "GND_GND") (pintype "bidirectional"))
      (node (ref "U2") (pin "12") (pinfunction "GND_12") (pintype "bidirectional"))
      (node (ref "U2") (pin "14") (pinfunction "GND_14") (pintype "bidirectional"))
      (node (ref "U2") (pin "8") (pinfunction "GND_8") (pintype "bidirectional"))
      (node (ref "U2") (pin "9") (pinfunction "GND_9") (pintype "bidirectional"))
      (node (ref "U2") (pin "GND") (pinfunction "GND_GND") (pintype "bidirectional"))
      (node (ref "U3") (pin "28") (pinfunction "DVSS_28") (pintype "bidirectional"))
      (node (ref "U3") (pin "7") (pinfunction "IOVSS_7") (pintype "bidirectional"))
      (node (ref "U3") (pin "GND") (pinfunction "GND_GND") (pintype "bidirectional"))
      (node (ref "U4") (pin "21") (pinfunction "GND3_21") (pintype "bidirectional"))
      (node (ref "U4") (pin "3") (pinfunction "GND1_3") (pintype "bidirectional"))
      (node (ref "U4") (pin "5") (pinfunction "GND2_5") (pintype "bidirectional"))
      (node (ref "U5") (pin "2") (pinfunction "GND_2") (pintype "bidirectional"))
      (node (ref "U5") (pin "4") (pinfunction "GND_4") (pintype "bidirectional"))
      (node (ref "U6") (pin "1") (pinfunction "NTC_1") (pintype "bidirectional"))
      (node (ref "U6") (pin "14") (pinfunction "D1_14") (pintype "bidirectional"))
      (node (ref "U6") (pin "4") (pinfunction "D2_4") (pintype "bidirectional"))
      (node (ref "U6") (pin "GND") (pinfunction "GND_GND") (pintype "bidirectional"))
      (node (ref "USB") (pin "5") (pinfunction "GND_5") (pintype "bidirectional"))
      (node (ref "USB") (pin "GND1") (pinfunction "GND_GND1") (pintype "bidirectional"))
      (node (ref "USB") (pin "GND2") (pinfunction "GND_GND2") (pintype "bidirectional"))
      (node (ref "USB") (pin "GND3") (pinfunction "GND_GND3") (pintype "bidirectional"))
      (node (ref "USB") (pin "GND4") (pinfunction "GND_GND4") (pintype "bidirectional"))
      (node (ref "X1") (pin "2") (pinfunction "CASE_2") (pintype "passive"))
      (node (ref "X1") (pin "4") (pinfunction "CASE_4") (pintype "passive"))
      (node (ref "X2") (pin "GND-1") (pinfunction "CASE_GND-1") (pintype "passive"))
      (node (ref "X2") (pin "GND-2") (pinfunction "CASE_GND-2") (pintype "passive"))
    )
    (net (code "35") (name "MCLK") (class "Default")
      (node (ref "L5") (pin "1") (pinfunction "1_1") (pintype "passive"))
      (node (ref "U3") (pin "1") (pinfunction "MCLK_1") (pintype "bidirectional"))
    )
    (net (code "36") (name "MISO") (class "Default")
      (node (ref "CCD") (pin "10") (pinfunction "10_10") (pintype "bidirectional"))
      (node (ref "ICSP") (pin "1") (pinfunction "1_1") (pintype "passive"))
      (node (ref "U1") (pin "6") (pinfunction "MISO_6") (pintype "bidirectional"))
      (node (ref "U3") (pin "11") (pinfunction "MISO/MFP4_11") (pintype "bidirectional"))
      (node (ref "U4") (pin "16") (pinfunction "PB4(MISO)_16") (pintype "bidirectional"))
    )
    (net (code "37") (name "MISO_SD") (class "Default")
      (node (ref "MICROSD") (pin "DAT0") (pinfunction "MISO_DAT0") (pintype "bidirectional"))
      (node (ref "U4") (pin "9") (pinfunction "PD5_9") (pintype "bidirectional"))
    )
    (net (code "38") (name "MOSI") (class "Default")
      (node (ref "CCD") (pin "8") (pinfunction "8_8") (pintype "bidirectional"))
      (node (ref "ICSP") (pin "4") (pinfunction "4_4") (pintype "passive"))
      (node (ref "U1") (pin "5") (pinfunction "MOSI_5") (pintype "bidirectional"))
      (node (ref "U3") (pin "10") (pinfunction "SDA/MOSI_10") (pintype "bidirectional"))
      (node (ref "U4") (pin "15") (pinfunction "PB3(MOSI)_15") (pintype "bidirectional"))
    )
    (net (code "39") (name "MOSI_SD") (class "Default")
      (node (ref "MICROSD") (pin "CMD") (pinfunction "MOSI_CMD") (pintype "bidirectional"))
      (node (ref "U4") (pin "11") (pinfunction "PD7(AIN1)_11") (pintype "bidirectional"))
    )
    (net (code "40") (name "Net-(AVR-PadA)") (class "Default")
      (node (ref "AVR") (pin "A") (pinfunction "A_A") (pintype "passive"))
      (node (ref "R14") (pin "1") (pinfunction "1_1") (pintype "passive"))
    )
    (net (code "41") (name "Net-(BATTERY-2)") (class "Default")
      (node (ref "BATTERY") (pin "1") (pinfunction "2_1") (pintype "passive"))
      (node (ref "Q1") (pin "2") (pinfunction "S_2") (pintype "passive"))
      (node (ref "U6") (pin "9") (pinfunction "BAT_9") (pintype "bidirectional"))
    )
    (net (code "42") (name "Net-(C25-Pad1)") (class "Default")
      (node (ref "C25") (pin "1") (pinfunction "1_1") (pintype "passive"))
      (node (ref "L8") (pin "2") (pinfunction "2_2") (pintype "passive"))
    )
    (net (code "43") (name "Net-(C25-Pad2)") (class "Default")
      (node (ref "C25") (pin "2") (pinfunction "2_2") (pintype "passive"))
      (node (ref "C26") (pin "1") (pinfunction "1_1") (pintype "passive"))
      (node (ref "C28") (pin "1") (pinfunction "1_1") (pintype "passive"))
      (node (ref "L10") (pin "2") (pinfunction "2_2") (pintype "passive"))
    )
    (net (code "44") (name "Net-(C26-Pad2)") (class "Default")
      (node (ref "C26") (pin "2") (pinfunction "2_2") (pintype "passive"))
      (node (ref "J1") (pin "SIG") (pinfunction "SIG_SIG") (pintype "bidirectional"))
    )
    (net (code "45") (name "Net-(C27-Pad1)") (class "Default")
      (node (ref "C27") (pin "1") (pinfunction "1_1") (pintype "passive"))
      (node (ref "L7") (pin "2") (pinfunction "2_2") (pintype "passive"))
      (node (ref "L8") (pin "1") (pinfunction "1_1") (pintype "passive"))
    )
    (net (code "46") (name "Net-(C54-Pad1)") (class "Default")
      (node (ref "C54") (pin "1") (pinfunction "1_1") (pintype "passive"))
      (node (ref "R19") (pin "1") (pinfunction "1_1") (pintype "passive"))
    )
    (net (code "47") (name "Net-(CC8531-PadA)") (class "Default")
      (node (ref "CC8531") (pin "A") (pinfunction "A_A") (pintype "passive"))
      (node (ref "R5") (pin "2") (pinfunction "2_2") (pintype "passive"))
    )
    (net (code "48") (name "Net-(CCD-Pad9)") (class "Default")
      (node (ref "CCD") (pin "9") (pinfunction "9_9") (pintype "bidirectional"))
      (node (ref "EXT") (pin "1") (pinfunction "1_1") (pintype "passive"))
    )
    (net (code "49") (name "Net-(CHARGE-PadA)") (class "Default")
      (node (ref "CHARGE") (pin "A") (pinfunction "A_A") (pintype "passive"))
      (node (ref "R18") (pin "1") (pinfunction "1_1") (pintype "passive"))
    )
    (net (code "50") (name "Net-(D1-C1)") (class "Default")
      (node (ref "D1") (pin "3") (pinfunction "C1_3") (pintype "passive"))
      (node (ref "L16") (pin "2") (pinfunction "2_2") (pintype "passive"))
    )
    (net (code "51") (name "Net-(D2-C1)") (class "Default")
      (node (ref "D2") (pin "3") (pinfunction "C1_3") (pintype "passive"))
      (node (ref "U5") (pin "1") (pinfunction "VIN_1") (pintype "bidirectional"))
    )
    (net (code "52") (name "Net-(J2B-S1-NC)") (class "Default")
      (node (ref "J2") (pin "6") (pinfunction "S1-NC_6") (pintype "bidirectional"))
      (node (ref "R22") (pin "1") (pinfunction "1_1") (pintype "passive"))
    )
    (net (code "53") (name "Net-(J2B-S1-NO)") (class "Default")
      (node (ref "J2") (pin "8") (pinfunction "S1-NO_8") (pintype "bidirectional"))
      (node (ref "R24") (pin "1") (pinfunction "1_1") (pintype "passive"))
    )
    (net (code "54") (name "Net-(J3B-S1-NC)") (class "Default")
      (node (ref "J3") (pin "6") (pinfunction "S1-NC_6") (pintype "bidirectional"))
      (node (ref "R25") (pin "1") (pinfunction "1_1") (pintype "passive"))
    )
    (net (code "55") (name "Net-(J3B-S1-NO)") (class "Default")
      (node (ref "J3") (pin "8") (pinfunction "S1-NO_8") (pintype "bidirectional"))
      (node (ref "R26") (pin "1") (pinfunction "1_1") (pintype "passive"))
    )
    (net (code "56") (name "Net-(POWER-PadA)") (class "Default")
      (node (ref "POWER") (pin "A") (pinfunction "A_A") (pintype "passive"))
      (node (ref "R3") (pin "1") (pinfunction "1_1") (pintype "passive"))
    )
    (net (code "57") (name "Net-(Q1-D)") (class "Default")
      (node (ref "C52") (pin "1") (pinfunction "1_1") (pintype "passive"))
      (node (ref "F1") (pin "1") (pinfunction "1_1") (pintype "passive"))
      (node (ref "L17") (pin "2") (pinfunction "2_2") (pintype "passive"))
      (node (ref "Q1") (pin "3") (pinfunction "D_3") (pintype "passive"))
      (node (ref "U6") (pin "10") (pinfunction "VOUT_10") (pintype "bidirectional"))
      (node (ref "U6") (pin "3") (pinfunction "VOUTS_3") (pintype "bidirectional"))
    )
    (net (code "58") (name "Net-(Q1-G)") (class "Default")
      (node (ref "Q1") (pin "1") (pinfunction "G_1") (pintype "passive"))
      (node (ref "U6") (pin "8") (pinfunction "GATE_8") (pintype "bidirectional"))
    )
    (net (code "59") (name "Net-(SW1-O)") (class "Default")
      (node (ref "F1") (pin "2") (pinfunction "2_2") (pintype "passive"))
      (node (ref "SW1") (pin "3") (pinfunction "O_3") (pintype "bidirectional"))
    )
    (net (code "60") (name "Net-(U1-AD0{slash}GIO7)") (class "Default")
      (node (ref "L11") (pin "2") (pinfunction "2_2") (pintype "passive"))
      (node (ref "U1") (pin "16") (pinfunction "AD0/GIO7_16") (pintype "bidirectional"))
    )
    (net (code "61") (name "Net-(U1-AD1{slash}GIO8)") (class "Default")
      (node (ref "L13") (pin "2") (pinfunction "2_2") (pintype "passive"))
      (node (ref "U1") (pin "17") (pinfunction "AD1/GIO8_17") (pintype "bidirectional"))
    )
    (net (code "62") (name "Net-(U1-AD2{slash}GIO9)") (class "Default")
      (node (ref "R7") (pin "1") (pinfunction "1_1") (pintype "passive"))
      (node (ref "U1") (pin "19") (pinfunction "AD2/GIO9_19") (pintype "bidirectional"))
    )
    (net (code "63") (name "Net-(U1-BCLK{slash}GIO5)") (class "Default")
      (node (ref "L6") (pin "2") (pinfunction "2_2") (pintype "passive"))
      (node (ref "U1") (pin "14") (pinfunction "BCLK/GIO5_14") (pintype "bidirectional"))
    )
    (net (code "64") (name "Net-(U1-DCPL)") (class "Default")
      (node (ref "C23") (pin "1") (pinfunction "1_1") (pintype "passive"))
      (node (ref "U1") (pin "39") (pinfunction "DCPL_39") (pintype "bidirectional"))
    )
    (net (code "65") (name "Net-(U1-GIO1)") (class "Default")
      (node (ref "CC8531_GIO") (pin "3") (pinfunction "P$2_3") (pintype "bidirectional"))
      (node (ref "CC8531_GIO") (pin "4") (pinfunction "P$2_4") (pintype "bidirectional"))
      (node (ref "U1") (pin "7") (pinfunction "GIO1_7") (pintype "bidirectional"))
    )
    (net (code "66") (name "Net-(U1-GIO3)") (class "Default")
      (node (ref "R5") (pin "1") (pinfunction "1_1") (pintype "passive"))
      (node (ref "U1") (pin "9") (pinfunction "GIO3_9") (pintype "bidirectional"))
    )
    (net (code "67") (name "Net-(U1-MCLK{slash}GIO4)") (class "Default")
      (node (ref "L5") (pin "2") (pinfunction "2_2") (pintype "passive"))
      (node (ref "U1") (pin "13") (pinfunction "MCLK/GIO4_13") (pintype "bidirectional"))
    )
    (net (code "68") (name "Net-(U1-RBIAS)") (class "Default")
      (node (ref "R4") (pin "2") (pinfunction "2_2") (pintype "passive"))
      (node (ref "U1") (pin "30") (pinfunction "RBIAS_30") (pintype "bidirectional"))
    )
    (net (code "69") (name "Net-(U1-RSTN)") (class "Default")
      (node (ref "L4") (pin "1") (pinfunction "1_1") (pintype "passive"))
      (node (ref "U1") (pin "11") (pinfunction "RSTN_11") (pintype "bidirectional"))
    )
    (net (code "70") (name "Net-(U1-USBN)") (class "Default")
      (node (ref "C14") (pin "1") (pinfunction "1_1") (pintype "passive"))
      (node (ref "R1") (pin "1") (pinfunction "1_1") (pintype "passive"))
      (node (ref "U1") (pin "1") (pinfunction "USBN_1") (pintype "bidirectional"))
    )
    (net (code "71") (name "Net-(U1-USBP)") (class "Default")
      (node (ref "C13") (pin "1") (pinfunction "1_1") (pintype "passive"))
      (node (ref "R2") (pin "1") (pinfunction "1_1") (pintype "passive"))
      (node (ref "U1") (pin "2") (pinfunction "USBP_2") (pintype "bidirectional"))
    )
    (net (code "72") (name "Net-(U1-WCLK{slash}GIO6)") (class "Default")
      (node (ref "L9") (pin "2") (pinfunction "2_2") (pintype "passive"))
      (node (ref "U1") (pin "15") (pinfunction "WCLK/GIO6_15") (pintype "bidirectional"))
    )
    (net (code "73") (name "Net-(U1-X0)") (class "Default")
      (node (ref "C24") (pin "1") (pinfunction "1_1") (pintype "passive"))
      (node (ref "U1") (pin "22") (pinfunction "X0_22") (pintype "bidirectional"))
      (node (ref "X1") (pin "3") (pinfunction "2_3") (pintype "passive"))
    )
    (net (code "74") (name "Net-(U1-X1)") (class "Default")
      (node (ref "C29") (pin "1") (pinfunction "1_1") (pintype "passive"))
      (node (ref "U1") (pin "21") (pinfunction "X1_21") (pintype "bidirectional"))
      (node (ref "X1") (pin "1") (pinfunction "1_1") (pintype "passive"))
    )
    (net (code "75") (name "Net-(U1-XPAEN)") (class "Default")
      (node (ref "L12") (pin "1") (pinfunction "1_1") (pintype "passive"))
      (node (ref "U1") (pin "36") (pinfunction "XPAEN_36") (pintype "bidirectional"))
    )
    (net (code "76") (name "Net-(U2-ANT)") (class "Default")
      (node (ref "L7") (pin "1") (pinfunction "1_1") (pintype "passive"))
      (node (ref "U2") (pin "11") (pinfunction "ANT_11") (pintype "bidirectional"))
    )
    (net (code "77") (name "Net-(U2-BIAS)") (class "Default")
      (node (ref "R8") (pin "2") (pinfunction "2_2") (pintype "passive"))
      (node (ref "U2") (pin "15") (pinfunction "BIAS_15") (pintype "bidirectional"))
    )
    (net (code "78") (name "Net-(U2-HGM)") (class "Default")
      (node (ref "R9") (pin "1") (pinfunction "1_1") (pintype "passive"))
      (node (ref "U2") (pin "7") (pinfunction "HGM_7") (pintype "bidirectional"))
    )
    (net (code "79") (name "Net-(U3-AVDD)") (class "Default")
      (node (ref "C48") (pin "1") (pinfunction "1_1") (pintype "passive"))
      (node (ref "U3") (pin "24") (pinfunction "AVDD_24") (pintype "bidirectional"))
    )
    (net (code "80") (name "Net-(U3-DVDD)") (class "Default")
      (node (ref "C49") (pin "1") (pinfunction "1_1") (pintype "passive"))
      (node (ref "U3") (pin "29") (pinfunction "DVDD_29") (pintype "bidirectional"))
    )
    (net (code "81") (name "Net-(U3-IN1_L)") (class "Default")
      (node (ref "C38") (pin "2") (pinfunction "2_2") (pintype "passive"))
      (node (ref "U3") (pin "13") (pinfunction "IN1_L_13") (pintype "bidirectional"))
    )
    (net (code "82") (name "Net-(U3-IN1_R)") (class "Default")
      (node (ref "C37") (pin "2") (pinfunction "2_2") (pintype "passive"))
      (node (ref "U3") (pin "14") (pinfunction "IN1_R_14") (pintype "bidirectional"))
    )
    (net (code "83") (name "Net-(U3-LOL)") (class "Default")
      (node (ref "R13") (pin "2") (pinfunction "2_2") (pintype "passive"))
      (node (ref "U3") (pin "22") (pinfunction "LOL_22") (pintype "bidirectional"))
    )
    (net (code "84") (name "Net-(U3-LOR)") (class "Default")
      (node (ref "R16") (pin "2") (pinfunction "2_2") (pintype "passive"))
      (node (ref "U3") (pin "23") (pinfunction "LOR_23") (pintype "bidirectional"))
    )
    (net (code "85") (name "Net-(U3-REF)") (class "Default")
      (node (ref "C50") (pin "1") (pinfunction "1_1") (pintype "passive"))
      (node (ref "U3") (pin "18") (pinfunction "REF_18") (pintype "bidirectional"))
    )
    (net (code "86") (name "Net-(U4-PB6(XTAL1))") (class "Default")
      (node (ref "C46") (pin "1") (pinfunction "1_1") (pintype "passive"))
      (node (ref "U4") (pin "7") (pinfunction "PB6(XTAL1)_7") (pintype "bidirectional"))
      (node (ref "X2") (pin "X1") (pinfunction "1_X1") (pintype "passive"))
    )
    (net (code "87") (name "Net-(U4-PB7(XTAL2))") (class "Default")
      (node (ref "C47") (pin "1") (pinfunction "1_1") (pintype "passive"))
      (node (ref "U4") (pin "8") (pinfunction "PB7(XTAL2)_8") (pintype "bidirectional"))
      (node (ref "X2") (pin "X2") (pinfunction "2_X2") (pintype "passive"))
    )
    (net (code "88") (name "Net-(U4-PD3)") (class "Default")
      (node (ref "R14") (pin "2") (pinfunction "2_2") (pintype "passive"))
      (node (ref "U4") (pin "1") (pinfunction "PD3_1") (pintype "bidirectional"))
    )
    (net (code "89") (name "Net-(U6-CLRPROG)") (class "Default")
      (node (ref "R19") (pin "2") (pinfunction "2_2") (pintype "passive"))
      (node (ref "R20") (pin "2") (pinfunction "2_2") (pintype "passive"))
      (node (ref "U6") (pin "2") (pinfunction "CLRPROG_2") (pintype "bidirectional"))
    )
    (net (code "90") (name "Net-(U6-C{slash}X)") (class "Default")
      (node (ref "R21") (pin "2") (pinfunction "2_2") (pintype "passive"))
      (node (ref "U6") (pin "5") (pinfunction "C/X_5") (pintype "bidirectional"))
      (node (ref "U6") (pin "6") (pinfunction "PROG_6") (pintype "bidirectional"))
    )
    (net (code "91") (name "Net-(U6-D0)") (class "Default")
      (node (ref "C51") (pin "1") (pinfunction "1_1") (pintype "passive"))
      (node (ref "R18") (pin "2") (pinfunction "2_2") (pintype "passive"))
      (node (ref "U6") (pin "11") (pinfunction "VBUS_11") (pintype "bidirectional"))
      (node (ref "U6") (pin "13") (pinfunction "D0_13") (pintype "bidirectional"))
      (node (ref "V_CHRG") (pin "2") (pinfunction "2_2") (pintype "passive"))
    )
    (net (code "92") (name "Net-(U6-SW)") (class "Default")
      (node (ref "L17") (pin "1") (pinfunction "1_1") (pintype "passive"))
      (node (ref "U6") (pin "12") (pinfunction "SW_12") (pintype "bidirectional"))
    )
    (net (code "93") (name "Net-(U6-~{CHRG})") (class "Default")
      (node (ref "CHARGE") (pin "C") (pinfunction "C_C") (pintype "passive"))
      (node (ref "U6") (pin "7") (pinfunction "~{CHRG}_7") (pintype "bidirectional"))
    )
    (net (code "94") (name "Net-(U7A--IN)") (class "Default")
      (node (ref "R12") (pin "2") (pinfunction "2_2") (pintype "passive"))
      (node (ref "R13") (pin "1") (pinfunction "1_1") (pintype "passive"))
      (node (ref "U7") (pin "2") (pinfunction "-IN_2") (pintype "input"))
    )
    (net (code "95") (name "Net-(U7A-OUT)") (class "Default")
      (node (ref "C36") (pin "1") (pinfunction "1_1") (pintype "passive"))
      (node (ref "R12") (pin "1") (pinfunction "1_1") (pintype "passive"))
      (node (ref "U7") (pin "1") (pinfunction "OUT_1") (pintype "output"))
    )
    (net (code "96") (name "Net-(U7B--IN)") (class "Default")
      (node (ref "R15") (pin "2") (pinfunction "2_2") (pintype "passive"))
      (node (ref "R16") (pin "1") (pinfunction "1_1") (pintype "passive"))
      (node (ref "U7") (pin "6") (pinfunction "-IN_6") (pintype "input"))
    )
    (net (code "97") (name "Net-(U7B-OUT)") (class "Default")
      (node (ref "C39") (pin "1") (pinfunction "1_1") (pintype "passive"))
      (node (ref "R15") (pin "1") (pinfunction "1_1") (pintype "passive"))
      (node (ref "U7") (pin "7") (pinfunction "OUT_7") (pintype "output"))
    )
    (net (code "98") (name "PROG_PWR") (class "Default")
      (node (ref "D1") (pin "2") (pinfunction "A_2") (pintype "passive"))
      (node (ref "ICSP") (pin "2") (pinfunction "2_2") (pintype "passive"))
      (node (ref "SERIAL") (pin "3") (pinfunction "3_3") (pintype "passive"))
    )
    (net (code "99") (name "RESET_AVR") (class "Default")
      (node (ref "C30") (pin "2") (pinfunction "2_2") (pintype "passive"))
      (node (ref "ICSP") (pin "5") (pinfunction "5_5") (pintype "passive"))
      (node (ref "R11") (pin "1") (pinfunction "1_1") (pintype "passive"))
      (node (ref "RESET_AVR") (pin "3") (pinfunction "P$2_3") (pintype "bidirectional"))
      (node (ref "RESET_AVR") (pin "4") (pinfunction "P$2_4") (pintype "bidirectional"))
      (node (ref "U4") (pin "29") (pinfunction "PC6(~{RESET})_29") (pintype "bidirectional"))
    )
    (net (code "100") (name "RESET_CC8531") (class "Default")
      (node (ref "CCD") (pin "7") (pinfunction "7_7") (pintype "bidirectional"))
      (node (ref "L4") (pin "2") (pinfunction "2_2") (pintype "passive"))
      (node (ref "U4") (pin "26") (pinfunction "PC3(ADC3)_26") (pintype "bidirectional"))
    )
    (net (code "101") (name "RESET_CODEC") (class "Default")
      (node (ref "U3") (pin "31") (pinfunction "~{RESET}_31") (pintype "bidirectional"))
      (node (ref "U4") (pin "13") (pinfunction "PB1_13") (pintype "bidirectional"))
    )
    (net (code "102") (name "SCLK") (class "Default")
      (node (ref "CCD") (pin "6") (pinfunction "6_6") (pintype "bidirectional"))
      (node (ref "ICSP") (pin "3") (pinfunction "3_3") (pintype "passive"))
      (node (ref "U1") (pin "4") (pinfunction "SCLK_4") (pintype "bidirectional"))
      (node (ref "U3") (pin "8") (pinfunction "SCLK/MFP3_8") (pintype "bidirectional"))
      (node (ref "U4") (pin "17") (pinfunction "PB5(SCK)_17") (pintype "bidirectional"))
    )
    (net (code "103") (name "SCLK_SD") (class "Default")
      (node (ref "MICROSD") (pin "CLK") (pinfunction "SCLK_CLK") (pintype "bidirectional"))
      (node (ref "U4") (pin "10") (pinfunction "PD6(AIN0)_10") (pintype "bidirectional"))
    )
    (net (code "104") (name "VBUS") (class "Default")
      (node (ref "USB") (pin "1") (pinfunction "VBUS_1") (pintype "bidirectional"))
      (node (ref "V_CHRG") (pin "1") (pinfunction "1_1") (pintype "passive"))
    )
    (net (code "105") (name "WCLK") (class "Default")
      (node (ref "L9") (pin "1") (pinfunction "1_1") (pintype "passive"))
      (node (ref "U3") (pin "3") (pinfunction "WCLK_3") (pintype "bidirectional"))
    )
    (net (code "106") (name "unconnected-(CCD-Pad3)") (class "Default")
      (node (ref "CCD") (pin "3") (pinfunction "3_3") (pintype "bidirectional"))
    )
    (net (code "107") (name "unconnected-(CCD-Pad4)") (class "Default")
      (node (ref "CCD") (pin "4") (pinfunction "4_4") (pintype "bidirectional"))
    )
    (net (code "108") (name "unconnected-(J2B-S2-NC-Pad9)") (class "Default")
      (node (ref "J2") (pin "9") (pinfunction "S2-NC_9") (pintype "bidirectional"))
    )
    (net (code "109") (name "unconnected-(J2B-S2-NO-Pad11)") (class "Default")
      (node (ref "J2") (pin "11") (pinfunction "S2-NO_11") (pintype "bidirectional"))
    )
    (net (code "110") (name "unconnected-(J2B-S2-Pad10)") (class "Default")
      (node (ref "J2") (pin "10") (pinfunction "S2_10") (pintype "bidirectional"))
    )
    (net (code "111") (name "unconnected-(J3B-S2-NC-Pad9)") (class "Default")
      (node (ref "J3") (pin "9") (pinfunction "S2-NC_9") (pintype "bidirectional"))
    )
    (net (code "112") (name "unconnected-(J3B-S2-NO-Pad11)") (class "Default")
      (node (ref "J3") (pin "11") (pinfunction "S2-NO_11") (pintype "bidirectional"))
    )
    (net (code "113") (name "unconnected-(J3B-S2-Pad10)") (class "Default")
      (node (ref "J3") (pin "10") (pinfunction "S2_10") (pintype "bidirectional"))
    )
    (net (code "114") (name "unconnected-(SW1-A-Pad1)") (class "Default")
      (node (ref "SW1") (pin "1") (pinfunction "A_1") (pintype "bidirectional"))
    )
    (net (code "115") (name "unconnected-(U1-SCL{slash}GIO10-Pad32)") (class "Default")
      (node (ref "U1") (pin "32") (pinfunction "SCL/GIO10_32") (pintype "bidirectional"))
    )
    (net (code "116") (name "unconnected-(U1-SDA{slash}GIO11-Pad33)") (class "Default")
      (node (ref "U1") (pin "33") (pinfunction "SDA/GIO11_33") (pintype "bidirectional"))
    )
    (net (code "117") (name "unconnected-(U2-RXTX-Pad3)") (class "Default")
      (node (ref "U2") (pin "3") (pinfunction "RXTX_3") (pintype "bidirectional"))
    )
    (net (code "118") (name "unconnected-(U3-GPIO{slash}MFP5-Pad32)") (class "Default")
      (node (ref "U3") (pin "32") (pinfunction "GPIO/MFP5_32") (pintype "bidirectional"))
    )
    (net (code "119") (name "unconnected-(U3-HPL-Pad25)") (class "Default")
      (node (ref "U3") (pin "25") (pinfunction "HPL_25") (pintype "bidirectional"))
    )
    (net (code "120") (name "unconnected-(U3-HPR-Pad27)") (class "Default")
      (node (ref "U3") (pin "27") (pinfunction "HPR_27") (pintype "bidirectional"))
    )
    (net (code "121") (name "unconnected-(U3-IN2_L-Pad15)") (class "Default")
      (node (ref "U3") (pin "15") (pinfunction "IN2_L_15") (pintype "bidirectional"))
    )
    (net (code "122") (name "unconnected-(U3-IN2_R-Pad16)") (class "Default")
      (node (ref "U3") (pin "16") (pinfunction "IN2_R_16") (pintype "bidirectional"))
    )
    (net (code "123") (name "unconnected-(U3-IN3_L-Pad20)") (class "Default")
      (node (ref "U3") (pin "20") (pinfunction "IN3_L_20") (pintype "bidirectional"))
    )
    (net (code "124") (name "unconnected-(U3-IN3_R-Pad21)") (class "Default")
      (node (ref "U3") (pin "21") (pinfunction "IN3_R_21") (pintype "bidirectional"))
    )
    (net (code "125") (name "unconnected-(U3-MICBIAS-Pad19)") (class "Default")
      (node (ref "U3") (pin "19") (pinfunction "MICBIAS_19") (pintype "bidirectional"))
    )
    (net (code "126") (name "unconnected-(U4-ADC6-Pad19)") (class "Default")
      (node (ref "U4") (pin "19") (pinfunction "ADC6_19") (pintype "bidirectional"))
    )
    (net (code "127") (name "unconnected-(U4-ADC7-Pad22)") (class "Default")
      (node (ref "U4") (pin "22") (pinfunction "ADC7_22") (pintype "bidirectional"))
    )
    (net (code "128") (name "unconnected-(U4-AREF-Pad20)") (class "Default")
      (node (ref "U4") (pin "20") (pinfunction "AREF_20") (pintype "bidirectional"))
    )
    (net (code "129") (name "unconnected-(U4-PB2(~{SS})-Pad14)") (class "Default")
      (node (ref "U4") (pin "14") (pinfunction "PB2(~{SS})_14") (pintype "bidirectional"))
    )
    (net (code "130") (name "unconnected-(U4-PC5(ADC5{slash}SCL)-Pad28)") (class "Default")
      (node (ref "U4") (pin "28") (pinfunction "PC5(ADC5/SCL)_28") (pintype "bidirectional"))
    )
    (net (code "131") (name "unconnected-(U4-PD2-Pad32)") (class "Default")
      (node (ref "U4") (pin "32") (pinfunction "PD2_32") (pintype "bidirectional"))
    )
    (net (code "132") (name "unconnected-(U4-PD4(XCK)-Pad2)") (class "Default")
      (node (ref "U4") (pin "2") (pinfunction "PD4(XCK)_2") (pintype "bidirectional"))
    )
    (net (code "133") (name "unconnected-(USB-ID-Pad4)") (class "Default")
      (node (ref "USB") (pin "4") (pinfunction "ID_4") (pintype "bidirectional"))
    )
  )
)
